# SHIELD_COMPLETO.net
KiCad netlist of a schematic drawn in EAGLE
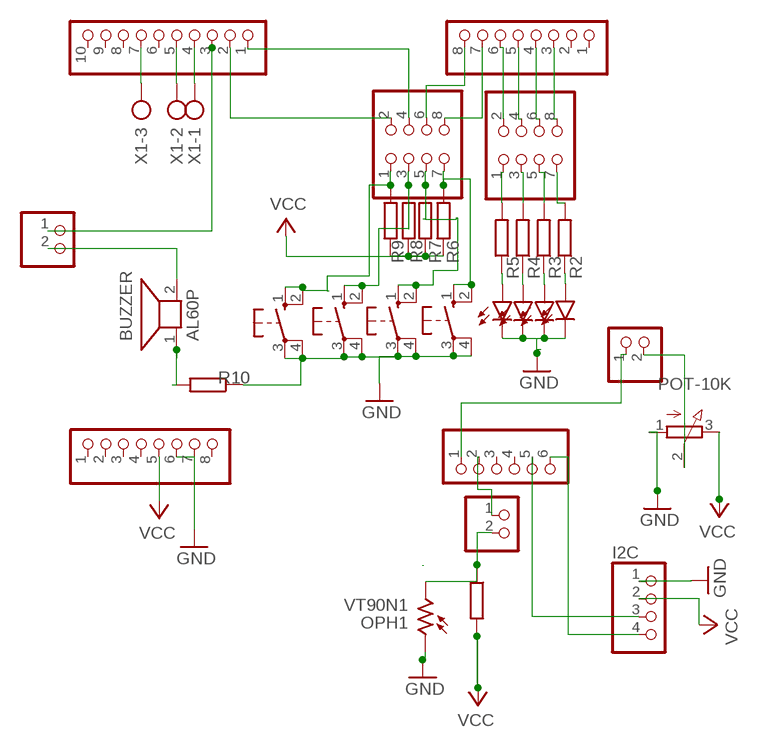
[diagram p0: schematic, sheet 1]

(export (version "E")
  (design (tool "Eeschema 10.0.6"))
  (components
    (comp (ref "AD")
      (value "6x1F-H8.5")
      (footprint "eagle-import:1X06")
      (libsource (lib "eagle-import") (part "PINHD-1X6"))
    )
    (comp (ref "BOT1")
      (value "10-XX")
      (footprint "eagle-import:B3F-10XX")
      (fields (field (name "MPN") "B3F-1000"))
      (libsource (lib "eagle-import") (part "10-XX"))
    )
    (comp (ref "BOT2")
      (value "10-XX")
      (footprint "eagle-import:B3F-10XX")
      (fields (field (name "MPN") "B3F-1000"))
      (libsource (lib "eagle-import") (part "10-XX"))
    )
    (comp (ref "BOT3")
      (value "10-XX")
      (footprint "eagle-import:B3F-10XX")
      (fields (field (name "MPN") "B3F-1000"))
      (libsource (lib "eagle-import") (part "10-XX"))
    )
    (comp (ref "BOT4")
      (value "10-XX")
      (footprint "eagle-import:B3F-10XX")
      (fields (field (name "MPN") "B3F-1000"))
      (libsource (lib "eagle-import") (part "10-XX"))
    )
    (comp (ref "BUZZER")
      (value "AL60P")
      (footprint "eagle-import:AL60P")
      (libsource (lib "eagle-import") (part "AL60P"))
    )
    (comp (ref "I2C")
      (value "PINHD-1X4")
      (footprint "eagle-import:1X04")
      (libsource (lib "eagle-import") (part "PINHD-1X4"))
    )
    (comp (ref "IOH")
      (value "10x1F-H8.5")
      (footprint "eagle-import:1X10")
      (libsource (lib "eagle-import") (part "PINHD-1X10_ARD"))
    )
    (comp (ref "IOL")
      (value "8x1F-H8.5")
      (footprint "eagle-import:1X08")
      (libsource (lib "eagle-import") (part "PINHD-1X8"))
    )
    (comp (ref "J10")
      (value "PINHD-1X2")
      (footprint "eagle-import:1X02")
      (libsource (lib "eagle-import") (part "PINHD-1X2"))
    )
    (comp (ref "JP1")
      (value "PINHD-2X4")
      (footprint "eagle-import:2X04")
      (libsource (lib "eagle-import") (part "PINHD-2X4"))
    )
    (comp (ref "JP2")
      (value "PINHD-2X4")
      (footprint "eagle-import:2X04")
      (libsource (lib "eagle-import") (part "PINHD-2X4"))
    )
    (comp (ref "JP3")
      (value "PINHD-1X2")
      (footprint "eagle-import:1X02")
      (libsource (lib "eagle-import") (part "PINHD-1X2"))
    )
    (comp (ref "JP4")
      (value "PINHD-1X2")
      (footprint "eagle-import:1X02")
      (libsource (lib "eagle-import") (part "PINHD-1X2"))
    )
    (comp (ref "LED1")
      (value "LED5MM")
      (footprint "eagle-import:LED5MM")
      (libsource (lib "eagle-import") (part "LED5MM"))
    )
    (comp (ref "LED2")
      (value "LED5MM")
      (footprint "eagle-import:LED5MM")
      (libsource (lib "eagle-import") (part "LED5MM"))
    )
    (comp (ref "LED3")
      (value "LED5MM")
      (footprint "eagle-import:LED5MM")
      (libsource (lib "eagle-import") (part "LED5MM"))
    )
    (comp (ref "LED4")
      (value "LED5MM")
      (footprint "eagle-import:LED5MM")
      (libsource (lib "eagle-import") (part "LED5MM"))
    )
    (comp (ref "OPH1")
      (value "VT90N1")
      (footprint "eagle-import:VT900")
      (libsource (lib "eagle-import") (part "VT90N1"))
    )
    (comp (ref "POT-10K")
      (value "3RP/1610N")
      (footprint "eagle-import:3RP_1610N")
      (libsource (lib "eagle-import") (part "3RP/1610N"))
    )
    (comp (ref "POWER")
      (value "8x1F-H8.5")
      (footprint "eagle-import:1X08")
      (libsource (lib "eagle-import") (part "PINHD-1X8"))
    )
    (comp (ref "R1")
      (value "R-EU_0204/7")
      (footprint "eagle-import:0204_7")
      (libsource (lib "eagle-import") (part "R-EU_0204/7"))
    )
    (comp (ref "R2")
      (value "R-EU_0204/7")
      (footprint "eagle-import:0204_7")
      (libsource (lib "eagle-import") (part "R-EU_0204/7"))
    )
    (comp (ref "R3")
      (value "R-EU_0204/7")
      (footprint "eagle-import:0204_7")
      (libsource (lib "eagle-import") (part "R-EU_0204/7"))
    )
    (comp (ref "R4")
      (value "R-EU_0204/7")
      (footprint "eagle-import:0204_7")
      (libsource (lib "eagle-import") (part "R-EU_0204/7"))
    )
    (comp (ref "R5")
      (value "R-EU_0204/7")
      (footprint "eagle-import:0204_7")
      (libsource (lib "eagle-import") (part "R-EU_0204/7"))
    )
    (comp (ref "R6")
      (value "R-EU_0204/7")
      (footprint "eagle-import:0204_7")
      (libsource (lib "eagle-import") (part "R-EU_0204/7"))
    )
    (comp (ref "R7")
      (value "R-EU_0204/7")
      (footprint "eagle-import:0204_7")
      (libsource (lib "eagle-import") (part "R-EU_0204/7"))
    )
    (comp (ref "R8")
      (value "R-EU_0204/7")
      (footprint "eagle-import:0204_7")
      (libsource (lib "eagle-import") (part "R-EU_0204/7"))
    )
    (comp (ref "R9")
      (value "R-EU_0204/7")
      (footprint "eagle-import:0204_7")
      (libsource (lib "eagle-import") (part "R-EU_0204/7"))
    )
    (comp (ref "R10")
      (value "R-EU_0204/7")
      (footprint "eagle-import:0204_7")
      (libsource (lib "eagle-import") (part "R-EU_0204/7"))
    )
    (comp (ref "X1")
      (value "AK300/3")
      (footprint "eagle-import:AK300_3")
      (libsource (lib "eagle-import") (part "AK300/3"))
    )
  )
  (nets
    (net (code "1") (name "GND") (class "Default")
      (node (ref "BOT1") (pin "3") (pinfunction "P_3") (pintype "passive"))
      (node (ref "BOT1") (pin "4") (pinfunction "P1_4") (pintype "passive"))
      (node (ref "BOT2") (pin "3") (pinfunction "P_3") (pintype "passive"))
      (node (ref "BOT2") (pin "4") (pinfunction "P1_4") (pintype "passive"))
      (node (ref "BOT3") (pin "3") (pinfunction "P_3") (pintype "passive"))
      (node (ref "BOT3") (pin "4") (pinfunction "P1_4") (pintype "passive"))
      (node (ref "BOT4") (pin "3") (pinfunction "P_3") (pintype "passive"))
      (node (ref "BOT4") (pin "4") (pinfunction "P1_4") (pintype "passive"))
      (node (ref "I2C") (pin "1") (pinfunction "1_1") (pintype "passive"))
      (node (ref "LED1") (pin "K") (pinfunction "C_K") (pintype "passive"))
      (node (ref "LED2") (pin "K") (pinfunction "C_K") (pintype "passive"))
      (node (ref "LED3") (pin "K") (pinfunction "C_K") (pintype "passive"))
      (node (ref "LED4") (pin "K") (pinfunction "C_K") (pintype "passive"))
      (node (ref "OPH1") (pin "1") (pinfunction "1_1") (pintype "passive"))
      (node (ref "POT-10K") (pin "1") (pinfunction "A_1") (pintype "passive"))
      (node (ref "POWER") (pin "6") (pinfunction "6_6") (pintype "passive"))
      (node (ref "POWER") (pin "7") (pinfunction "7_7") (pintype "passive"))
      (node (ref "R10") (pin "1") (pinfunction "1_1") (pintype "passive"))
    )
    (net (code "2") (name "Net-(AD-Pad1)") (class "Default")
      (node (ref "AD") (pin "1") (pinfunction "1_1") (pintype "passive"))
      (node (ref "JP4") (pin "1") (pinfunction "1_1") (pintype "passive"))
    )
    (net (code "3") (name "Net-(AD-Pad2)") (class "Default")
      (node (ref "AD") (pin "2") (pinfunction "2_2") (pintype "passive"))
      (node (ref "JP3") (pin "1") (pinfunction "1_1") (pintype "passive"))
    )
    (net (code "4") (name "Net-(AD-Pad5)") (class "Default")
      (node (ref "AD") (pin "5") (pinfunction "5_5") (pintype "passive"))
      (node (ref "I2C") (pin "3") (pinfunction "3_3") (pintype "passive"))
    )
    (net (code "5") (name "Net-(AD-Pad6)") (class "Default")
      (node (ref "AD") (pin "6") (pinfunction "6_6") (pintype "passive"))
      (node (ref "I2C") (pin "4") (pinfunction "4_4") (pintype "passive"))
    )
    (net (code "6") (name "Net-(BOT1-S)") (class "Default")
      (node (ref "BOT1") (pin "1") (pinfunction "S_1") (pintype "passive"))
      (node (ref "BOT1") (pin "2") (pinfunction "S1_2") (pintype "passive"))
      (node (ref "JP2") (pin "7") (pinfunction "7_7") (pintype "passive"))
      (node (ref "R6") (pin "2") (pinfunction "2_2") (pintype "passive"))
    )
    (net (code "7") (name "Net-(BOT2-S)") (class "Default")
      (node (ref "BOT2") (pin "1") (pinfunction "S_1") (pintype "passive"))
      (node (ref "BOT2") (pin "2") (pinfunction "S1_2") (pintype "passive"))
      (node (ref "JP2") (pin "5") (pinfunction "5_5") (pintype "passive"))
      (node (ref "R7") (pin "2") (pinfunction "2_2") (pintype "passive"))
    )
    (net (code "8") (name "Net-(BOT3-S)") (class "Default")
      (node (ref "BOT3") (pin "1") (pinfunction "S_1") (pintype "passive"))
      (node (ref "BOT3") (pin "2") (pinfunction "S1_2") (pintype "passive"))
      (node (ref "JP2") (pin "3") (pinfunction "3_3") (pintype "passive"))
      (node (ref "R8") (pin "2") (pinfunction "2_2") (pintype "passive"))
    )
    (net (code "9") (name "Net-(BOT4-S)") (class "Default")
      (node (ref "BOT4") (pin "1") (pinfunction "S_1") (pintype "passive"))
      (node (ref "BOT4") (pin "2") (pinfunction "S1_2") (pintype "passive"))
      (node (ref "JP2") (pin "1") (pinfunction "1_1") (pintype "passive"))
      (node (ref "R9") (pin "2") (pinfunction "2_2") (pintype "passive"))
    )
    (net (code "10") (name "Net-(BUZZER-Pad1)") (class "Default")
      (node (ref "BUZZER") (pin "1") (pinfunction "1_1") (pintype "passive"))
      (node (ref "R10") (pin "2") (pinfunction "2_2") (pintype "passive"))
    )
    (net (code "11") (name "Net-(BUZZER-Pad2)") (class "Default")
      (node (ref "BUZZER") (pin "2") (pinfunction "2_2") (pintype "passive"))
      (node (ref "J10") (pin "2") (pinfunction "2_2") (pintype "passive"))
    )
    (net (code "12") (name "Net-(IOH-Pad1)") (class "Default")
      (node (ref "IOH") (pin "1") (pinfunction "1_1") (pintype "passive"))
      (node (ref "JP2") (pin "4") (pinfunction "4_4") (pintype "passive"))
    )
    (net (code "13") (name "Net-(IOH-Pad2)") (class "Default")
      (node (ref "IOH") (pin "2") (pinfunction "2_2") (pintype "passive"))
      (node (ref "JP2") (pin "2") (pinfunction "2_2") (pintype "passive"))
    )
    (net (code "14") (name "Net-(IOH-Pad3)") (class "Default")
      (node (ref "IOH") (pin "3") (pinfunction "3_3") (pintype "passive"))
      (node (ref "J10") (pin "1") (pinfunction "1_1") (pintype "passive"))
    )
    (net (code "15") (name "Net-(IOL-Pad3)") (class "Default")
      (node (ref "IOL") (pin "3") (pinfunction "3_3") (pintype "passive"))
      (node (ref "JP1") (pin "8") (pinfunction "8_8") (pintype "passive"))
    )
    (net (code "16") (name "Net-(IOL-Pad4)") (class "Default")
      (node (ref "IOL") (pin "4") (pinfunction "4_4") (pintype "passive"))
      (node (ref "JP1") (pin "6") (pinfunction "6_6") (pintype "passive"))
    )
    (net (code "17") (name "Net-(IOL-Pad5)") (class "Default")
      (node (ref "IOL") (pin "5") (pinfunction "5_5") (pintype "passive"))
      (node (ref "JP1") (pin "4") (pinfunction "4_4") (pintype "passive"))
    )
    (net (code "18") (name "Net-(IOL-Pad6)") (class "Default")
      (node (ref "IOL") (pin "6") (pinfunction "6_6") (pintype "passive"))
      (node (ref "JP1") (pin "2") (pinfunction "2_2") (pintype "passive"))
    )
    (net (code "19") (name "Net-(IOL-Pad7)") (class "Default")
      (node (ref "IOL") (pin "7") (pinfunction "7_7") (pintype "passive"))
      (node (ref "JP2") (pin "8") (pinfunction "8_8") (pintype "passive"))
    )
    (net (code "20") (name "Net-(IOL-Pad8)") (class "Default")
      (node (ref "IOL") (pin "8") (pinfunction "8_8") (pintype "passive"))
      (node (ref "JP2") (pin "6") (pinfunction "6_6") (pintype "passive"))
    )
    (net (code "21") (name "Net-(JP1-Pad1)") (class "Default")
      (node (ref "JP1") (pin "1") (pinfunction "1_1") (pintype "passive"))
      (node (ref "R5") (pin "2") (pinfunction "2_2") (pintype "passive"))
    )
    (net (code "22") (name "Net-(JP1-Pad3)") (class "Default")
      (node (ref "JP1") (pin "3") (pinfunction "3_3") (pintype "passive"))
      (node (ref "R4") (pin "2") (pinfunction "2_2") (pintype "passive"))
    )
    (net (code "23") (name "Net-(JP1-Pad5)") (class "Default")
      (node (ref "JP1") (pin "5") (pinfunction "5_5") (pintype "passive"))
      (node (ref "R3") (pin "2") (pinfunction "2_2") (pintype "passive"))
    )
    (net (code "24") (name "Net-(JP1-Pad7)") (class "Default")
      (node (ref "JP1") (pin "7") (pinfunction "7_7") (pintype "passive"))
      (node (ref "R2") (pin "2") (pinfunction "2_2") (pintype "passive"))
    )
    (net (code "25") (name "Net-(JP3-Pad2)") (class "Default")
      (node (ref "JP3") (pin "2") (pinfunction "2_2") (pintype "passive"))
      (node (ref "OPH1") (pin "2") (pinfunction "2_2") (pintype "passive"))
      (node (ref "R1") (pin "1") (pinfunction "1_1") (pintype "passive"))
    )
    (net (code "26") (name "Net-(LED1-PadA)") (class "Default")
      (node (ref "LED1") (pin "A") (pinfunction "A_A") (pintype "passive"))
      (node (ref "R2") (pin "1") (pinfunction "1_1") (pintype "passive"))
    )
    (net (code "27") (name "Net-(LED2-PadA)") (class "Default")
      (node (ref "LED2") (pin "A") (pinfunction "A_A") (pintype "passive"))
      (node (ref "R3") (pin "1") (pinfunction "1_1") (pintype "passive"))
    )
    (net (code "28") (name "Net-(LED3-PadA)") (class "Default")
      (node (ref "LED3") (pin "A") (pinfunction "A_A") (pintype "passive"))
      (node (ref "R4") (pin "1") (pinfunction "1_1") (pintype "passive"))
    )
    (net (code "29") (name "Net-(LED4-PadA)") (class "Default")
      (node (ref "LED4") (pin "A") (pinfunction "A_A") (pintype "passive"))
      (node (ref "R5") (pin "1") (pinfunction "1_1") (pintype "passive"))
    )
    (net (code "30") (name "Net-(POT-10K-S)") (class "Default")
      (node (ref "JP4") (pin "2") (pinfunction "2_2") (pintype "passive"))
      (node (ref "POT-10K") (pin "2") (pinfunction "S_2") (pintype "passive"))
    )
    (net (code "31") (name "Net-(X1A-KL)") (class "Default")
      (node (ref "IOH") (pin "4") (pinfunction "4_4") (pintype "passive"))
      (node (ref "X1") (pin "1") (pinfunction "KL_1") (pintype "passive"))
    )
    (net (code "32") (name "Net-(X1B-KL)") (class "Default")
      (node (ref "IOH") (pin "5") (pinfunction "5_5") (pintype "passive"))
      (node (ref "X1") (pin "2") (pinfunction "KL_2") (pintype "passive"))
    )
    (net (code "33") (name "Net-(X1C-KL)") (class "Default")
      (node (ref "IOH") (pin "7") (pinfunction "7_7") (pintype "passive"))
      (node (ref "X1") (pin "3") (pinfunction "KL_3") (pintype "passive"))
    )
    (net (code "34") (name "VCC") (class "Default")
      (node (ref "I2C") (pin "2") (pinfunction "2_2") (pintype "passive"))
      (node (ref "POT-10K") (pin "3") (pinfunction "E_3") (pintype "passive"))
      (node (ref "POWER") (pin "5") (pinfunction "5_5") (pintype "passive"))
      (node (ref "R1") (pin "2") (pinfunction "2_2") (pintype "passive"))
      (node (ref "R6") (pin "1") (pinfunction "1_1") (pintype "passive"))
      (node (ref "R7") (pin "1") (pinfunction "1_1") (pintype "passive"))
      (node (ref "R8") (pin "1") (pinfunction "1_1") (pintype "passive"))
      (node (ref "R9") (pin "1") (pinfunction "1_1") (pintype "passive"))
    )
    (net (code "35") (name "unconnected-(AD-Pad3)") (class "Default")
      (node (ref "AD") (pin "3") (pinfunction "3_3") (pintype "passive"))
    )
    (net (code "36") (name "unconnected-(AD-Pad4)") (class "Default")
      (node (ref "AD") (pin "4") (pinfunction "4_4") (pintype "passive"))
    )
    (net (code "37") (name "unconnected-(IOH-Pad6)") (class "Default")
      (node (ref "IOH") (pin "6") (pinfunction "6_6") (pintype "passive"))
    )
    (net (code "38") (name "unconnected-(IOH-Pad8)") (class "Default")
      (node (ref "IOH") (pin "8") (pinfunction "8_8") (pintype "passive"))
    )
    (net (code "39") (name "unconnected-(IOH-Pad9)") (class "Default")
      (node (ref "IOH") (pin "9") (pinfunction "9_9") (pintype "passive"))
    )
    (net (code "40") (name "unconnected-(IOH-Pad10)") (class "Default")
      (node (ref "IOH") (pin "10") (pinfunction "10_10") (pintype "passive"))
    )
    (net (code "41") (name "unconnected-(IOL-Pad1)") (class "Default")
      (node (ref "IOL") (pin "1") (pinfunction "1_1") (pintype "passive"))
    )
    (net (code "42") (name "unconnected-(IOL-Pad2)") (class "Default")
      (node (ref "IOL") (pin "2") (pinfunction "2_2") (pintype "passive"))
    )
    (net (code "43") (name "unconnected-(POWER-Pad1)") (class "Default")
      (node (ref "POWER") (pin "1") (pinfunction "1_1") (pintype "passive"))
    )
    (net (code "44") (name "unconnected-(POWER-Pad2)") (class "Default")
      (node (ref "POWER") (pin "2") (pinfunction "2_2") (pintype "passive"))
    )
    (net (code "45") (name "unconnected-(POWER-Pad3)") (class "Default")
      (node (ref "POWER") (pin "3") (pinfunction "3_3") (pintype "passive"))
    )
    (net (code "46") (name "unconnected-(POWER-Pad4)") (class "Default")
      (node (ref "POWER") (pin "4") (pinfunction "4_4") (pintype "passive"))
    )
    (net (code "47") (name "unconnected-(POWER-Pad8)") (class "Default")
      (node (ref "POWER") (pin "8") (pinfunction "8_8") (pintype "passive"))
    )
  )
)
